# powerTestv1-1.net
KiCad netlist of a schematic drawn in EAGLE
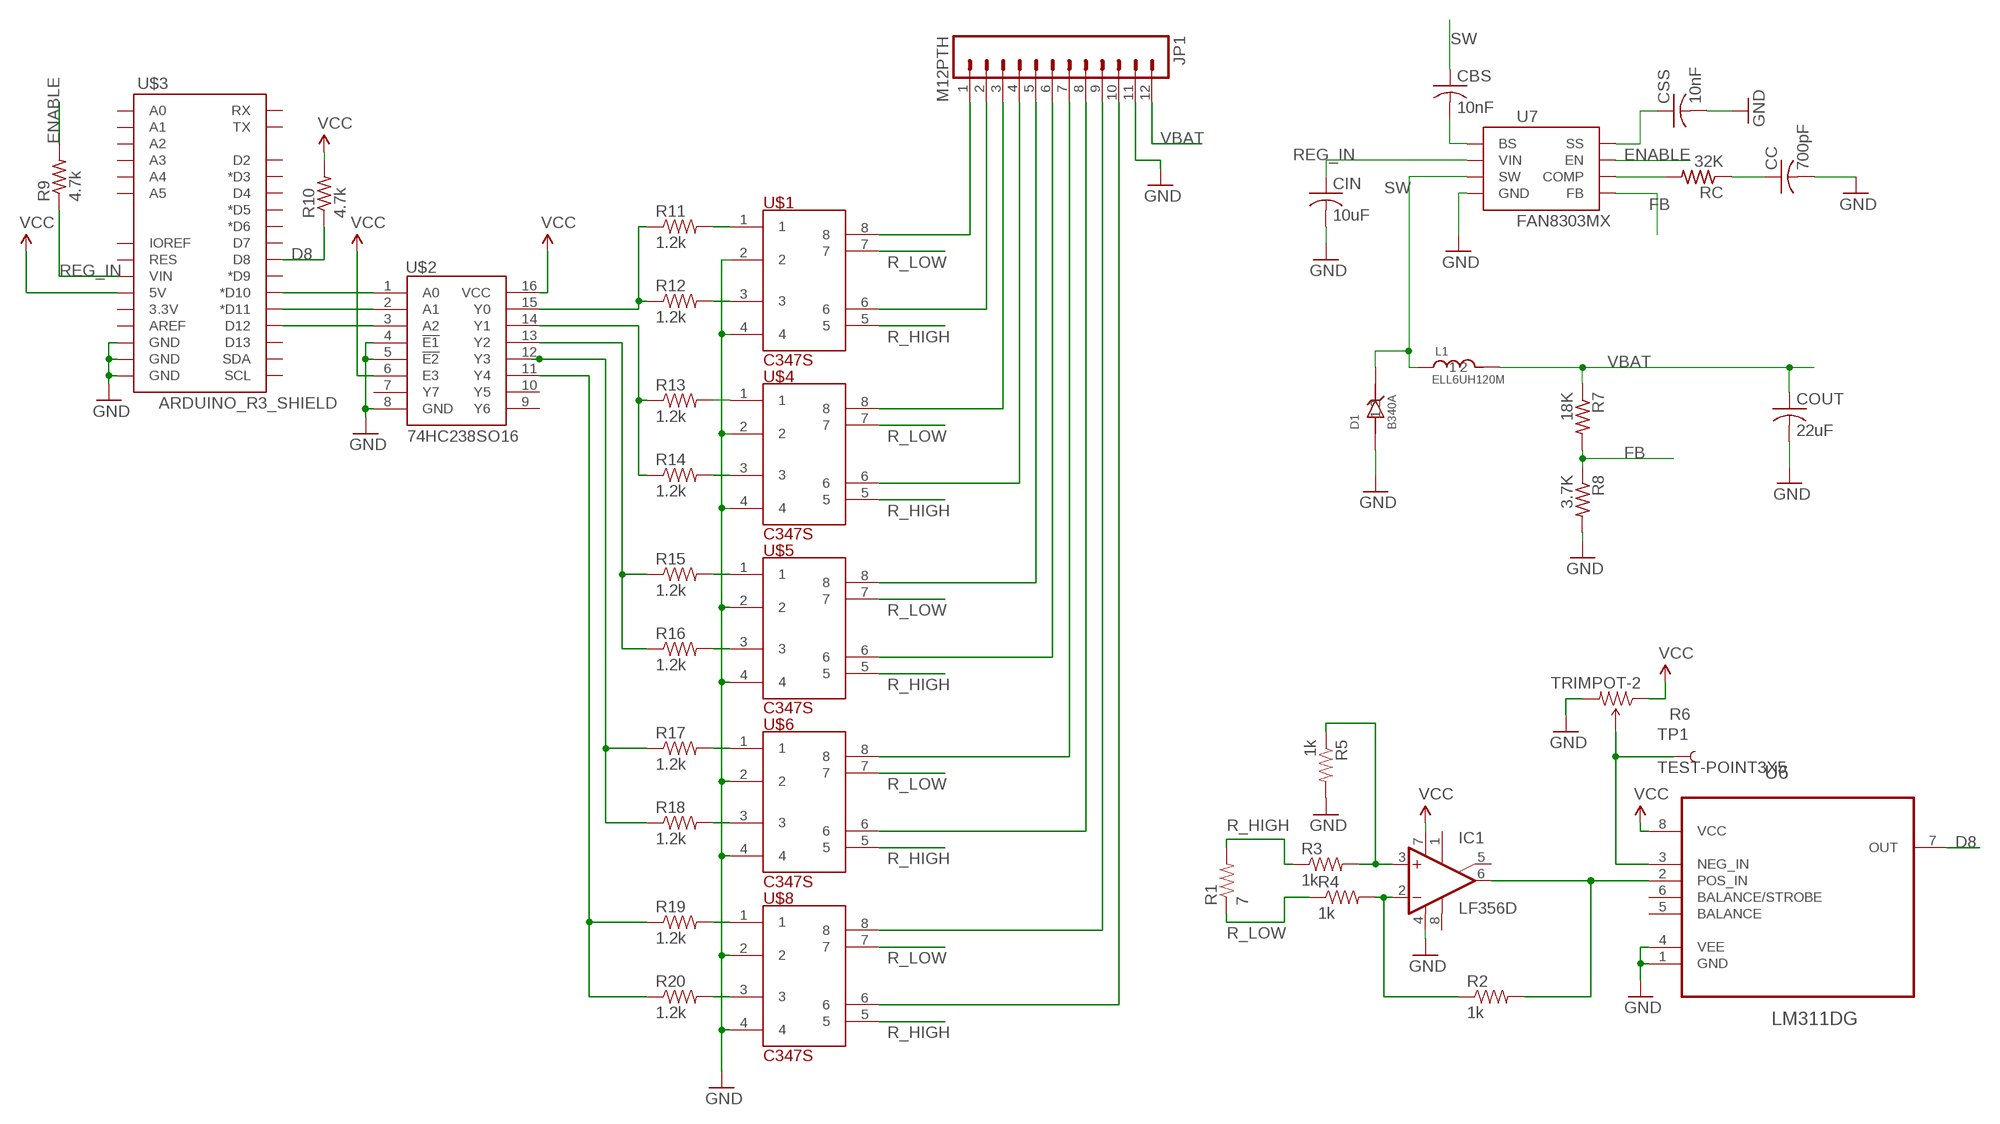
[diagram p0: schematic, sheet 1]

(export (version "E")
  (design (tool "Eeschema 10.0.6"))
  (components
    (comp (ref "CBS")
      (value "10nF")
      (footprint "eagle-import:C0603")
      (libsource (lib "eagle-import") (part "C-USC0603"))
    )
    (comp (ref "CC")
      (value "700pF")
      (footprint "eagle-import:C0603")
      (libsource (lib "eagle-import") (part "C-USC0603"))
    )
    (comp (ref "CIN")
      (value "10uF")
      (footprint "eagle-import:C0603")
      (libsource (lib "eagle-import") (part "C-USC0603"))
    )
    (comp (ref "COUT")
      (value "22uF")
      (footprint "eagle-import:C0603")
      (libsource (lib "eagle-import") (part "C-USC0603"))
    )
    (comp (ref "CSS")
      (value "10nF")
      (footprint "eagle-import:C0603")
      (libsource (lib "eagle-import") (part "C-USC0603"))
    )
    (comp (ref "D1")
      (value "B340A")
      (footprint "eagle-import:B340A")
      (libsource (lib "eagle-import") (part "B340A"))
    )
    (comp (ref "IC1")
      (value "LF356D")
      (footprint "eagle-import:SO08")
      (libsource (lib "eagle-import") (part "LF356D"))
    )
    (comp (ref "JP1")
      (value "M12PTH")
      (footprint "eagle-import:1X12")
      (libsource (lib "eagle-import") (part "M12PTH"))
    )
    (comp (ref "L1")
      (value "ELL6UH120M")
      (footprint "eagle-import:ELL6UH120M")
      (libsource (lib "eagle-import") (part "ELL6UH120M"))
    )
    (comp (ref "R1")
      (value "7")
      (footprint "eagle-import:AXIAL-0.8")
      (libsource (lib "eagle-import") (part "SparkFun-Resistors_RESISTORPTH-2W"))
    )
    (comp (ref "R2")
      (value "1k")
      (footprint "eagle-import:0603-RES")
      (libsource (lib "eagle-import") (part "RESISTOR0603-RES"))
    )
    (comp (ref "R3")
      (value "1k")
      (footprint "eagle-import:0603-RES")
      (libsource (lib "eagle-import") (part "RESISTOR0603-RES"))
    )
    (comp (ref "R4")
      (value "1k")
      (footprint "eagle-import:0603-RES")
      (libsource (lib "eagle-import") (part "RESISTOR0603-RES"))
    )
    (comp (ref "R5")
      (value "1k")
      (footprint "eagle-import:0603-RES")
      (libsource (lib "eagle-import") (part "RESISTOR0603-RES"))
    )
    (comp (ref "R6")
      (value "TRIMPOT-2")
      (footprint "eagle-import:TRIMPOT_TC33")
      (libsource (lib "eagle-import") (part "TRIMPOT-2"))
    )
    (comp (ref "R7")
      (value "18K")
      (footprint "eagle-import:R0603")
      (libsource (lib "eagle-import") (part "R-US_R0603"))
    )
    (comp (ref "R8")
      (value "3.7K")
      (footprint "eagle-import:R0603")
      (libsource (lib "eagle-import") (part "R-US_R0603"))
    )
    (comp (ref "R9")
      (value "4.7k")
      (footprint "eagle-import:R0603")
      (libsource (lib "eagle-import") (part "R-US_R0603"))
    )
    (comp (ref "R10")
      (value "4.7k")
      (footprint "eagle-import:R0603")
      (libsource (lib "eagle-import") (part "R-US_R0603"))
    )
    (comp (ref "R11")
      (value "1.2k")
      (footprint "eagle-import:0603-RES")
      (libsource (lib "eagle-import") (part "RESISTOR0603-RES"))
    )
    (comp (ref "R12")
      (value "1.2k")
      (footprint "eagle-import:0603-RES")
      (libsource (lib "eagle-import") (part "RESISTOR0603-RES"))
    )
    (comp (ref "R13")
      (value "1.2k")
      (footprint "eagle-import:0603-RES")
      (libsource (lib "eagle-import") (part "RESISTOR0603-RES"))
    )
    (comp (ref "R14")
      (value "1.2k")
      (footprint "eagle-import:0603-RES")
      (libsource (lib "eagle-import") (part "RESISTOR0603-RES"))
    )
    (comp (ref "R15")
      (value "1.2k")
      (footprint "eagle-import:0603-RES")
      (libsource (lib "eagle-import") (part "RESISTOR0603-RES"))
    )
    (comp (ref "R16")
      (value "1.2k")
      (footprint "eagle-import:0603-RES")
      (libsource (lib "eagle-import") (part "RESISTOR0603-RES"))
    )
    (comp (ref "R17")
      (value "1.2k")
      (footprint "eagle-import:0603-RES")
      (libsource (lib "eagle-import") (part "RESISTOR0603-RES"))
    )
    (comp (ref "R18")
      (value "1.2k")
      (footprint "eagle-import:0603-RES")
      (libsource (lib "eagle-import") (part "RESISTOR0603-RES"))
    )
    (comp (ref "R19")
      (value "1.2k")
      (footprint "eagle-import:0603-RES")
      (libsource (lib "eagle-import") (part "RESISTOR0603-RES"))
    )
    (comp (ref "R20")
      (value "1.2k")
      (footprint "eagle-import:0603-RES")
      (libsource (lib "eagle-import") (part "RESISTOR0603-RES"))
    )
    (comp (ref "RC")
      (value "32K")
      (footprint "eagle-import:R0603")
      (libsource (lib "eagle-import") (part "R-US_R0603"))
    )
    (comp (ref "TP1")
      (value "TEST-POINT3X5")
      (footprint "eagle-import:PAD.03X.05")
      (libsource (lib "eagle-import") (part "TEST-POINT3X5"))
    )
    (comp (ref "U$1")
      (value "C347S")
      (footprint "eagle-import:SOP8")
      (libsource (lib "eagle-import") (part "C347S"))
    )
    (comp (ref "U$2")
      (value "74HC238SO16")
      (footprint "eagle-import:SO16")
      (libsource (lib "eagle-import") (part "74HC238SO16"))
    )
    (comp (ref "U$3")
      (value "ARDUINO_R3_SHIELD")
      (footprint "eagle-import:UNO_R3_SHIELD")
      (libsource (lib "eagle-import") (part "ARDUINO_R3_SHIELD"))
    )
    (comp (ref "U$4")
      (value "C347S")
      (footprint "eagle-import:SOP8")
      (libsource (lib "eagle-import") (part "C347S"))
    )
    (comp (ref "U$5")
      (value "C347S")
      (footprint "eagle-import:SOP8")
      (libsource (lib "eagle-import") (part "C347S"))
    )
    (comp (ref "U$6")
      (value "C347S")
      (footprint "eagle-import:SOP8")
      (libsource (lib "eagle-import") (part "C347S"))
    )
    (comp (ref "U$8")
      (value "C347S")
      (footprint "eagle-import:SOP8")
      (libsource (lib "eagle-import") (part "C347S"))
    )
    (comp (ref "U6")
      (value "LM311DG")
      (footprint "eagle-import:SOIC127P600X175-8N")
      (libsource (lib "eagle-import") (part "LM311DG"))
    )
    (comp (ref "U7")
      (value "FAN8303MX")
      (footprint "eagle-import:FAN8303MX")
      (libsource (lib "eagle-import") (part "FAN8303MX"))
    )
  )
  (nets
    (net (code "1") (name "/D8") (class "Default")
      (node (ref "R10") (pin "1") (pinfunction "1_1") (pintype "passive"))
      (node (ref "U$3") (pin "D8") (pinfunction "D8_D8") (pintype "bidirectional"))
      (node (ref "U6") (pin "7") (pinfunction "OUT_7") (pintype "output"))
    )
    (net (code "2") (name "/ENABLE") (class "Default")
      (node (ref "R9") (pin "2") (pinfunction "2_2") (pintype "passive"))
      (node (ref "U7") (pin "P$7") (pinfunction "EN_P$7") (pintype "bidirectional"))
    )
    (net (code "3") (name "/FB") (class "Default")
      (node (ref "R7") (pin "2") (pinfunction "2_2") (pintype "passive"))
      (node (ref "R8") (pin "1") (pinfunction "1_1") (pintype "passive"))
      (node (ref "U7") (pin "P$5") (pinfunction "FB_P$5") (pintype "bidirectional"))
    )
    (net (code "4") (name "/REG_IN") (class "Default")
      (node (ref "CIN") (pin "1") (pinfunction "1_1") (pintype "passive"))
      (node (ref "R9") (pin "1") (pinfunction "1_1") (pintype "passive"))
      (node (ref "U$3") (pin "VIN") (pinfunction "VIN_VIN") (pintype "bidirectional"))
      (node (ref "U7") (pin "P$2") (pinfunction "VIN_P$2") (pintype "bidirectional"))
    )
    (net (code "5") (name "/R_HIGH") (class "Default")
      (node (ref "R1") (pin "P$2") (pinfunction "2_P$2") (pintype "passive"))
      (node (ref "R3") (pin "1") (pinfunction "1_1") (pintype "passive"))
      (node (ref "U$1") (pin "5") (pinfunction "5_5") (pintype "bidirectional"))
      (node (ref "U$4") (pin "5") (pinfunction "5_5") (pintype "bidirectional"))
      (node (ref "U$5") (pin "5") (pinfunction "5_5") (pintype "bidirectional"))
      (node (ref "U$6") (pin "5") (pinfunction "5_5") (pintype "bidirectional"))
      (node (ref "U$8") (pin "5") (pinfunction "5_5") (pintype "bidirectional"))
    )
    (net (code "6") (name "/R_LOW") (class "Default")
      (node (ref "R1") (pin "P$1") (pinfunction "1_P$1") (pintype "passive"))
      (node (ref "R4") (pin "1") (pinfunction "1_1") (pintype "passive"))
      (node (ref "U$1") (pin "7") (pinfunction "7_7") (pintype "bidirectional"))
      (node (ref "U$4") (pin "7") (pinfunction "7_7") (pintype "bidirectional"))
      (node (ref "U$5") (pin "7") (pinfunction "7_7") (pintype "bidirectional"))
      (node (ref "U$6") (pin "7") (pinfunction "7_7") (pintype "bidirectional"))
      (node (ref "U$8") (pin "7") (pinfunction "7_7") (pintype "bidirectional"))
    )
    (net (code "7") (name "/SW") (class "Default")
      (node (ref "CBS") (pin "1") (pinfunction "1_1") (pintype "passive"))
      (node (ref "D1") (pin "P$2") (pinfunction "2_P$2") (pintype "bidirectional"))
      (node (ref "L1") (pin "P$1") (pinfunction "1_P$1") (pintype "bidirectional"))
      (node (ref "U7") (pin "P$3") (pinfunction "SW_P$3") (pintype "bidirectional"))
    )
    (net (code "8") (name "/VBAT") (class "Default")
      (node (ref "COUT") (pin "1") (pinfunction "1_1") (pintype "passive"))
      (node (ref "JP1") (pin "12") (pinfunction "12_12") (pintype "passive"))
      (node (ref "L1") (pin "P$2") (pinfunction "2_P$2") (pintype "bidirectional"))
      (node (ref "R7") (pin "1") (pinfunction "1_1") (pintype "passive"))
    )
    (net (code "9") (name "GND") (class "Default")
      (node (ref "CC") (pin "2") (pinfunction "2_2") (pintype "passive"))
      (node (ref "CIN") (pin "2") (pinfunction "2_2") (pintype "passive"))
      (node (ref "COUT") (pin "2") (pinfunction "2_2") (pintype "passive"))
      (node (ref "CSS") (pin "2") (pinfunction "2_2") (pintype "passive"))
      (node (ref "D1") (pin "P$1") (pinfunction "1_P$1") (pintype "bidirectional"))
      (node (ref "IC1") (pin "4") (pinfunction "V-_4") (pintype "power_in"))
      (node (ref "JP1") (pin "11") (pinfunction "11_11") (pintype "passive"))
      (node (ref "R5") (pin "2") (pinfunction "2_2") (pintype "passive"))
      (node (ref "R6") (pin "3") (pinfunction "CW_3") (pintype "passive"))
      (node (ref "R8") (pin "2") (pinfunction "2_2") (pintype "passive"))
      (node (ref "U$1") (pin "2") (pinfunction "2_2") (pintype "bidirectional"))
      (node (ref "U$1") (pin "4") (pinfunction "4_4") (pintype "bidirectional"))
      (node (ref "U$2") (pin "4") (pinfunction "~{E1}_4") (pintype "input"))
      (node (ref "U$2") (pin "5") (pinfunction "~{E2}_5") (pintype "input"))
      (node (ref "U$2") (pin "8") (pinfunction "GND_8") (pintype "power_in"))
      (node (ref "U$3") (pin "GND@0") (pinfunction "GND_GND@0") (pintype "bidirectional"))
      (node (ref "U$3") (pin "GND@1") (pinfunction "GND_GND@1") (pintype "bidirectional"))
      (node (ref "U$3") (pin "GND@2") (pinfunction "GND_GND@2") (pintype "bidirectional"))
      (node (ref "U$4") (pin "2") (pinfunction "2_2") (pintype "bidirectional"))
      (node (ref "U$4") (pin "4") (pinfunction "4_4") (pintype "bidirectional"))
      (node (ref "U$5") (pin "2") (pinfunction "2_2") (pintype "bidirectional"))
      (node (ref "U$5") (pin "4") (pinfunction "4_4") (pintype "bidirectional"))
      (node (ref "U$6") (pin "2") (pinfunction "2_2") (pintype "bidirectional"))
      (node (ref "U$6") (pin "4") (pinfunction "4_4") (pintype "bidirectional"))
      (node (ref "U$8") (pin "2") (pinfunction "2_2") (pintype "bidirectional"))
      (node (ref "U$8") (pin "4") (pinfunction "4_4") (pintype "bidirectional"))
      (node (ref "U6") (pin "1") (pinfunction "GND_1") (pintype "passive"))
      (node (ref "U6") (pin "4") (pinfunction "VEE_4") (pintype "power_in"))
      (node (ref "U7") (pin "P$4") (pinfunction "GND_P$4") (pintype "bidirectional"))
    )
    (net (code "10") (name "Net-(CC-Pad1)") (class "Default")
      (node (ref "CC") (pin "1") (pinfunction "1_1") (pintype "passive"))
      (node (ref "RC") (pin "1") (pinfunction "1_1") (pintype "passive"))
    )
    (net (code "11") (name "Net-(IC1-+IN)") (class "Default")
      (node (ref "IC1") (pin "3") (pinfunction "+IN_3") (pintype "input"))
      (node (ref "R3") (pin "2") (pinfunction "2_2") (pintype "passive"))
      (node (ref "R5") (pin "1") (pinfunction "1_1") (pintype "passive"))
    )
    (net (code "12") (name "Net-(IC1--IN)") (class "Default")
      (node (ref "IC1") (pin "2") (pinfunction "-IN_2") (pintype "input"))
      (node (ref "R2") (pin "1") (pinfunction "1_1") (pintype "passive"))
      (node (ref "R4") (pin "2") (pinfunction "2_2") (pintype "passive"))
    )
    (net (code "13") (name "Net-(IC1-OUT)") (class "Default")
      (node (ref "IC1") (pin "6") (pinfunction "OUT_6") (pintype "output"))
      (node (ref "R2") (pin "2") (pinfunction "2_2") (pintype "passive"))
      (node (ref "U6") (pin "2") (pinfunction "POS_IN_2") (pintype "input"))
    )
    (net (code "14") (name "Net-(JP1-Pad1)") (class "Default")
      (node (ref "JP1") (pin "1") (pinfunction "1_1") (pintype "passive"))
      (node (ref "U$1") (pin "8") (pinfunction "8_8") (pintype "bidirectional"))
    )
    (net (code "15") (name "Net-(JP1-Pad2)") (class "Default")
      (node (ref "JP1") (pin "2") (pinfunction "2_2") (pintype "passive"))
      (node (ref "U$1") (pin "6") (pinfunction "6_6") (pintype "bidirectional"))
    )
    (net (code "16") (name "Net-(JP1-Pad3)") (class "Default")
      (node (ref "JP1") (pin "3") (pinfunction "3_3") (pintype "passive"))
      (node (ref "U$4") (pin "8") (pinfunction "8_8") (pintype "bidirectional"))
    )
    (net (code "17") (name "Net-(JP1-Pad4)") (class "Default")
      (node (ref "JP1") (pin "4") (pinfunction "4_4") (pintype "passive"))
      (node (ref "U$4") (pin "6") (pinfunction "6_6") (pintype "bidirectional"))
    )
    (net (code "18") (name "Net-(JP1-Pad5)") (class "Default")
      (node (ref "JP1") (pin "5") (pinfunction "5_5") (pintype "passive"))
      (node (ref "U$5") (pin "8") (pinfunction "8_8") (pintype "bidirectional"))
    )
    (net (code "19") (name "Net-(JP1-Pad6)") (class "Default")
      (node (ref "JP1") (pin "6") (pinfunction "6_6") (pintype "passive"))
      (node (ref "U$5") (pin "6") (pinfunction "6_6") (pintype "bidirectional"))
    )
    (net (code "20") (name "Net-(JP1-Pad7)") (class "Default")
      (node (ref "JP1") (pin "7") (pinfunction "7_7") (pintype "passive"))
      (node (ref "U$6") (pin "8") (pinfunction "8_8") (pintype "bidirectional"))
    )
    (net (code "21") (name "Net-(JP1-Pad8)") (class "Default")
      (node (ref "JP1") (pin "8") (pinfunction "8_8") (pintype "passive"))
      (node (ref "U$6") (pin "6") (pinfunction "6_6") (pintype "bidirectional"))
    )
    (net (code "22") (name "Net-(JP1-Pad9)") (class "Default")
      (node (ref "JP1") (pin "9") (pinfunction "9_9") (pintype "passive"))
      (node (ref "U$8") (pin "8") (pinfunction "8_8") (pintype "bidirectional"))
    )
    (net (code "23") (name "Net-(JP1-Pad10)") (class "Default")
      (node (ref "JP1") (pin "10") (pinfunction "10_10") (pintype "passive"))
      (node (ref "U$8") (pin "6") (pinfunction "6_6") (pintype "bidirectional"))
    )
    (net (code "24") (name "Net-(R6-WIPER)") (class "Default")
      (node (ref "R6") (pin "2") (pinfunction "WIPER_2") (pintype "passive"))
      (node (ref "TP1") (pin "P$1") (pinfunction "1_P$1") (pintype "bidirectional"))
      (node (ref "U6") (pin "3") (pinfunction "NEG_IN_3") (pintype "input"))
    )
    (net (code "25") (name "Net-(R11-Pad2)") (class "Default")
      (node (ref "R11") (pin "2") (pinfunction "2_2") (pintype "passive"))
      (node (ref "U$1") (pin "1") (pinfunction "1_1") (pintype "bidirectional"))
    )
    (net (code "26") (name "Net-(R12-Pad2)") (class "Default")
      (node (ref "R12") (pin "2") (pinfunction "2_2") (pintype "passive"))
      (node (ref "U$1") (pin "3") (pinfunction "3_3") (pintype "bidirectional"))
    )
    (net (code "27") (name "Net-(R13-Pad2)") (class "Default")
      (node (ref "R13") (pin "2") (pinfunction "2_2") (pintype "passive"))
      (node (ref "U$4") (pin "1") (pinfunction "1_1") (pintype "bidirectional"))
    )
    (net (code "28") (name "Net-(R14-Pad2)") (class "Default")
      (node (ref "R14") (pin "2") (pinfunction "2_2") (pintype "passive"))
      (node (ref "U$4") (pin "3") (pinfunction "3_3") (pintype "bidirectional"))
    )
    (net (code "29") (name "Net-(R15-Pad2)") (class "Default")
      (node (ref "R15") (pin "2") (pinfunction "2_2") (pintype "passive"))
      (node (ref "U$5") (pin "1") (pinfunction "1_1") (pintype "bidirectional"))
    )
    (net (code "30") (name "Net-(R16-Pad2)") (class "Default")
      (node (ref "R16") (pin "2") (pinfunction "2_2") (pintype "passive"))
      (node (ref "U$5") (pin "3") (pinfunction "3_3") (pintype "bidirectional"))
    )
    (net (code "31") (name "Net-(R17-Pad2)") (class "Default")
      (node (ref "R17") (pin "2") (pinfunction "2_2") (pintype "passive"))
      (node (ref "U$6") (pin "1") (pinfunction "1_1") (pintype "bidirectional"))
    )
    (net (code "32") (name "Net-(R18-Pad2)") (class "Default")
      (node (ref "R18") (pin "2") (pinfunction "2_2") (pintype "passive"))
      (node (ref "U$6") (pin "3") (pinfunction "3_3") (pintype "bidirectional"))
    )
    (net (code "33") (name "Net-(R19-Pad2)") (class "Default")
      (node (ref "R19") (pin "2") (pinfunction "2_2") (pintype "passive"))
      (node (ref "U$8") (pin "1") (pinfunction "1_1") (pintype "bidirectional"))
    )
    (net (code "34") (name "Net-(R20-Pad2)") (class "Default")
      (node (ref "R20") (pin "2") (pinfunction "2_2") (pintype "passive"))
      (node (ref "U$8") (pin "3") (pinfunction "3_3") (pintype "bidirectional"))
    )
    (net (code "35") (name "Net-(U$2-A0)") (class "Default")
      (node (ref "U$2") (pin "1") (pinfunction "A0_1") (pintype "input"))
      (node (ref "U$3") (pin "D10") (pinfunction "*D10_D10") (pintype "bidirectional"))
    )
    (net (code "36") (name "Net-(U$2-A1)") (class "Default")
      (node (ref "U$2") (pin "2") (pinfunction "A1_2") (pintype "input"))
      (node (ref "U$3") (pin "D11") (pinfunction "*D11_D11") (pintype "bidirectional"))
    )
    (net (code "37") (name "Net-(U$2-A2)") (class "Default")
      (node (ref "U$2") (pin "3") (pinfunction "A2_3") (pintype "input"))
      (node (ref "U$3") (pin "D12") (pinfunction "D12_D12") (pintype "bidirectional"))
    )
    (net (code "38") (name "Net-(U$2-Y0)") (class "Default")
      (node (ref "R11") (pin "1") (pinfunction "1_1") (pintype "passive"))
      (node (ref "R12") (pin "1") (pinfunction "1_1") (pintype "passive"))
      (node (ref "U$2") (pin "15") (pinfunction "Y0_15") (pintype "output"))
    )
    (net (code "39") (name "Net-(U$2-Y1)") (class "Default")
      (node (ref "R13") (pin "1") (pinfunction "1_1") (pintype "passive"))
      (node (ref "R14") (pin "1") (pinfunction "1_1") (pintype "passive"))
      (node (ref "U$2") (pin "14") (pinfunction "Y1_14") (pintype "output"))
    )
    (net (code "40") (name "Net-(U$2-Y2)") (class "Default")
      (node (ref "R15") (pin "1") (pinfunction "1_1") (pintype "passive"))
      (node (ref "R16") (pin "1") (pinfunction "1_1") (pintype "passive"))
      (node (ref "U$2") (pin "13") (pinfunction "Y2_13") (pintype "output"))
    )
    (net (code "41") (name "Net-(U$2-Y3)") (class "Default")
      (node (ref "R17") (pin "1") (pinfunction "1_1") (pintype "passive"))
      (node (ref "R18") (pin "1") (pinfunction "1_1") (pintype "passive"))
      (node (ref "U$2") (pin "12") (pinfunction "Y3_12") (pintype "output"))
    )
    (net (code "42") (name "Net-(U$2-Y4)") (class "Default")
      (node (ref "R19") (pin "1") (pinfunction "1_1") (pintype "passive"))
      (node (ref "R20") (pin "1") (pinfunction "1_1") (pintype "passive"))
      (node (ref "U$2") (pin "11") (pinfunction "Y4_11") (pintype "output"))
    )
    (net (code "43") (name "Net-(U7-BS)") (class "Default")
      (node (ref "CBS") (pin "2") (pinfunction "2_2") (pintype "passive"))
      (node (ref "U7") (pin "P$1") (pinfunction "BS_P$1") (pintype "bidirectional"))
    )
    (net (code "44") (name "Net-(U7-COMP)") (class "Default")
      (node (ref "RC") (pin "2") (pinfunction "2_2") (pintype "passive"))
      (node (ref "U7") (pin "P$6") (pinfunction "COMP_P$6") (pintype "bidirectional"))
    )
    (net (code "45") (name "Net-(U7-SS)") (class "Default")
      (node (ref "CSS") (pin "1") (pinfunction "1_1") (pintype "passive"))
      (node (ref "U7") (pin "P$8") (pinfunction "SS_P$8") (pintype "bidirectional"))
    )
    (net (code "46") (name "VCC") (class "Default")
      (node (ref "IC1") (pin "7") (pinfunction "V+_7") (pintype "power_in"))
      (node (ref "R10") (pin "2") (pinfunction "2_2") (pintype "passive"))
      (node (ref "R6") (pin "1") (pinfunction "CCW_1") (pintype "passive"))
      (node (ref "U$2") (pin "16") (pinfunction "VCC_16") (pintype "power_in"))
      (node (ref "U$2") (pin "6") (pinfunction "E3_6") (pintype "input"))
      (node (ref "U$3") (pin "5V") (pinfunction "5V_5V") (pintype "bidirectional"))
      (node (ref "U6") (pin "8") (pinfunction "VCC_8") (pintype "power_in"))
    )
    (net (code "47") (name "unconnected-(IC1-ON1-Pad1)") (class "Default")
      (node (ref "IC1") (pin "1") (pinfunction "ON1_1") (pintype "passive"))
    )
    (net (code "48") (name "unconnected-(IC1-ON2-Pad5)") (class "Default")
      (node (ref "IC1") (pin "5") (pinfunction "ON2_5") (pintype "passive"))
    )
    (net (code "49") (name "unconnected-(IC1-OPT-Pad8)") (class "Default")
      (node (ref "IC1") (pin "8") (pinfunction "OPT_8") (pintype "passive"))
    )
    (net (code "50") (name "unconnected-(U$2-Y5-Pad10)") (class "Default")
      (node (ref "U$2") (pin "10") (pinfunction "Y5_10") (pintype "output"))
    )
    (net (code "51") (name "unconnected-(U$2-Y6-Pad9)") (class "Default")
      (node (ref "U$2") (pin "9") (pinfunction "Y6_9") (pintype "output"))
    )
    (net (code "52") (name "unconnected-(U$2-Y7-Pad7)") (class "Default")
      (node (ref "U$2") (pin "7") (pinfunction "Y7_7") (pintype "output"))
    )
    (net (code "53") (name "unconnected-(U$3-*D3-PadD3)") (class "Default")
      (node (ref "U$3") (pin "D3") (pinfunction "*D3_D3") (pintype "bidirectional"))
    )
    (net (code "54") (name "unconnected-(U$3-*D5-PadD5)") (class "Default")
      (node (ref "U$3") (pin "D5") (pinfunction "*D5_D5") (pintype "bidirectional"))
    )
    (net (code "55") (name "unconnected-(U$3-*D6-PadD6)") (class "Default")
      (node (ref "U$3") (pin "D6") (pinfunction "*D6_D6") (pintype "bidirectional"))
    )
    (net (code "56") (name "unconnected-(U$3-*D9-PadD9)") (class "Default")
      (node (ref "U$3") (pin "D9") (pinfunction "*D9_D9") (pintype "bidirectional"))
    )
    (net (code "57") (name "unconnected-(U$3-Pad3.3V)") (class "Default")
      (node (ref "U$3") (pin "3.3V") (pinfunction "3.3V_3.3V") (pintype "bidirectional"))
    )
    (net (code "58") (name "unconnected-(U$3-PadA0)") (class "Default")
      (node (ref "U$3") (pin "A0") (pinfunction "A0_A0") (pintype "bidirectional"))
    )
    (net (code "59") (name "unconnected-(U$3-PadA1)") (class "Default")
      (node (ref "U$3") (pin "A1") (pinfunction "A1_A1") (pintype "bidirectional"))
    )
    (net (code "60") (name "unconnected-(U$3-PadA2)") (class "Default")
      (node (ref "U$3") (pin "A2") (pinfunction "A2_A2") (pintype "bidirectional"))
    )
    (net (code "61") (name "unconnected-(U$3-PadA3)") (class "Default")
      (node (ref "U$3") (pin "A3") (pinfunction "A3_A3") (pintype "bidirectional"))
    )
    (net (code "62") (name "unconnected-(U$3-PadA4)") (class "Default")
      (node (ref "U$3") (pin "A4") (pinfunction "A4_A4") (pintype "bidirectional"))
    )
    (net (code "63") (name "unconnected-(U$3-PadA5)") (class "Default")
      (node (ref "U$3") (pin "A5") (pinfunction "A5_A5") (pintype "bidirectional"))
    )
    (net (code "64") (name "unconnected-(U$3-PadAREF)") (class "Default")
      (node (ref "U$3") (pin "AREF") (pinfunction "AREF_AREF") (pintype "bidirectional"))
    )
    (net (code "65") (name "unconnected-(U$3-PadD2)") (class "Default")
      (node (ref "U$3") (pin "D2") (pinfunction "D2_D2") (pintype "bidirectional"))
    )
    (net (code "66") (name "unconnected-(U$3-PadD4)") (class "Default")
      (node (ref "U$3") (pin "D4") (pinfunction "D4_D4") (pintype "bidirectional"))
    )
    (net (code "67") (name "unconnected-(U$3-PadD7)") (class "Default")
      (node (ref "U$3") (pin "D7") (pinfunction "D7_D7") (pintype "bidirectional"))
    )
    (net (code "68") (name "unconnected-(U$3-PadD13)") (class "Default")
      (node (ref "U$3") (pin "D13") (pinfunction "D13_D13") (pintype "bidirectional"))
    )
    (net (code "69") (name "unconnected-(U$3-PadIOREF)") (class "Default")
      (node (ref "U$3") (pin "IOREF") (pinfunction "IOREF_IOREF") (pintype "bidirectional"))
    )
    (net (code "70") (name "unconnected-(U$3-PadRES)") (class "Default")
      (node (ref "U$3") (pin "RES") (pinfunction "RES_RES") (pintype "bidirectional"))
    )
    (net (code "71") (name "unconnected-(U$3-PadRX)") (class "Default")
      (node (ref "U$3") (pin "RX") (pinfunction "RX_RX") (pintype "bidirectional"))
    )
    (net (code "72") (name "unconnected-(U$3-PadSCL)") (class "Default")
      (node (ref "U$3") (pin "SCL") (pinfunction "SCL_SCL") (pintype "bidirectional"))
    )
    (net (code "73") (name "unconnected-(U$3-PadSDA)") (class "Default")
      (node (ref "U$3") (pin "SDA") (pinfunction "SDA_SDA") (pintype "bidirectional"))
    )
    (net (code "74") (name "unconnected-(U$3-PadTX)") (class "Default")
      (node (ref "U$3") (pin "TX") (pinfunction "TX_TX") (pintype "bidirectional"))
    )
    (net (code "75") (name "unconnected-(U6-BALANCE-Pad5)") (class "Default")
      (node (ref "U6") (pin "5") (pinfunction "BALANCE_5") (pintype "input"))
    )
    (net (code "76") (name "unconnected-(U6-BALANCE{slash}STROBE-Pad6)") (class "Default")
      (node (ref "U6") (pin "6") (pinfunction "BALANCE/STROBE_6") (pintype "input"))
    )
  )
)
